# Rev2_Logicar.net
KiCad netlist of a schematic drawn in EAGLE
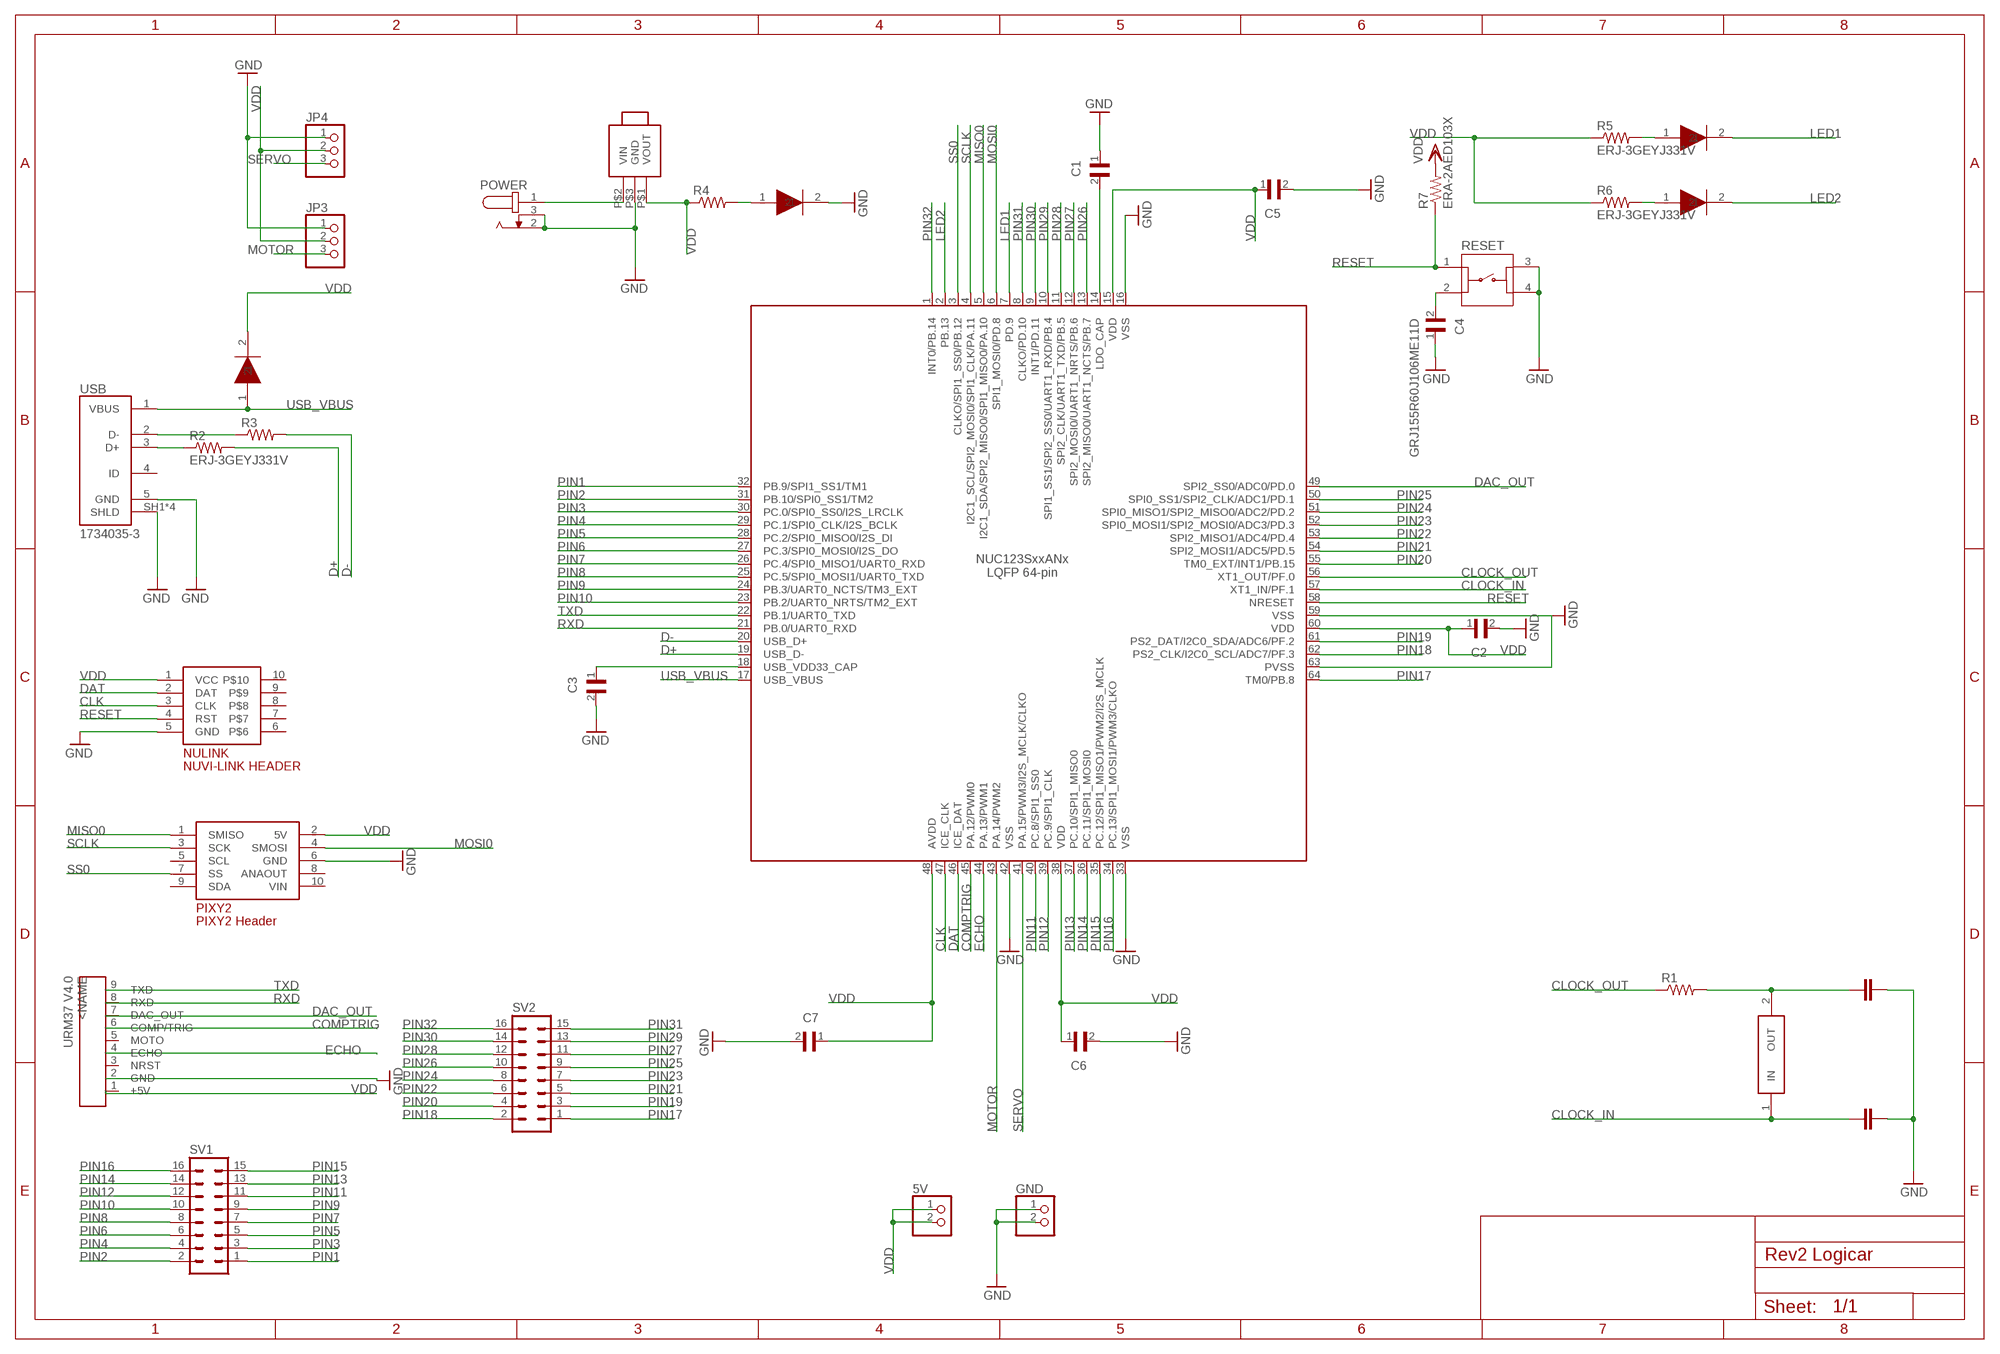
[diagram p0: schematic, sheet 1]

(export (version "E")
  (design (tool "Eeschema 10.0.6"))
  (components
    (comp (ref "5V")
      (value "PINHD-1X2")
      (footprint "eagle-import:1X02")
      (libsource (lib "eagle-import") (part "PINHD-1X2"))
    )
    (comp (ref "18UF")
      (value "18UF_CAPACITOR")
      (footprint "eagle-import:CAPC1608X70")
      (libsource (lib "eagle-import") (part "18UF_CAPACITOR"))
    )
    (comp (ref "18UF1")
      (value "18UF_CAPACITOR")
      (footprint "eagle-import:CAPC1608X70")
      (libsource (lib "eagle-import") (part "18UF_CAPACITOR"))
    )
    (comp (ref "C1")
      (value "F380J476MMAAXEH3")
      (footprint "eagle-import:CAPC1608X90")
      (fields (field (name "MF") "AVX"))
      (libsource (lib "eagle-import") (part "F380J476MMAAXEH3"))
    )
    (comp (ref "C2")
      (value "CL21F104ZBCNNNC")
      (footprint "eagle-import:CAPC2012X140N")
      (fields
        (field (name "DIGI-KEY_PART_NUMBER") "1276-1007-1-ND")
        (field (name "MF") "Samsung Electro-Mechanics")
      )
      (libsource (lib "eagle-import") (part "CL21F104ZBCNNNC"))
    )
    (comp (ref "C3")
      (value "CL21F104ZBCNNNC")
      (footprint "eagle-import:CAPC2012X140N")
      (fields
        (field (name "DIGI-KEY_PART_NUMBER") "1276-1007-1-ND")
        (field (name "MF") "Samsung Electro-Mechanics")
      )
      (libsource (lib "eagle-import") (part "CL21F104ZBCNNNC"))
    )
    (comp (ref "C4")
      (value "GRJ155R60J106ME11D")
      (footprint "eagle-import:CAPC1005X55N")
      (fields (field (name "DIGI-KEY_PART_NUMBER") "490-13211-1-ND") (field (name "MF") "Murata"))
      (libsource (lib "eagle-import") (part "GRJ155R60J106ME11D"))
    )
    (comp (ref "C5")
      (value "CL21F104ZBCNNNC")
      (footprint "eagle-import:CAPC2012X140N")
      (fields
        (field (name "DIGI-KEY_PART_NUMBER") "1276-1007-1-ND")
        (field (name "MF") "Samsung Electro-Mechanics")
      )
      (libsource (lib "eagle-import") (part "CL21F104ZBCNNNC"))
    )
    (comp (ref "C6")
      (value "CL21F104ZBCNNNC")
      (footprint "eagle-import:CAPC2012X140N")
      (fields
        (field (name "DIGI-KEY_PART_NUMBER") "1276-1007-1-ND")
        (field (name "MF") "Samsung Electro-Mechanics")
      )
      (libsource (lib "eagle-import") (part "CL21F104ZBCNNNC"))
    )
    (comp (ref "C7")
      (value "CL21F104ZBCNNNC")
      (footprint "eagle-import:CAPC2012X140N")
      (fields
        (field (name "DIGI-KEY_PART_NUMBER") "1276-1007-1-ND")
        (field (name "MF") "Samsung Electro-Mechanics")
      )
      (libsource (lib "eagle-import") (part "CL21F104ZBCNNNC"))
    )
    (comp (ref "GND")
      (value "PINHD-1X2")
      (footprint "eagle-import:1X02")
      (libsource (lib "eagle-import") (part "PINHD-1X2"))
    )
    (comp (ref "JP3")
      (value "PINHD-1X3")
      (footprint "eagle-import:1X03")
      (libsource (lib "eagle-import") (part "PINHD-1X3"))
    )
    (comp (ref "JP4")
      (value "PINHD-1X3")
      (footprint "eagle-import:1X03")
      (libsource (lib "eagle-import") (part "PINHD-1X3"))
    )
    (comp (ref "LED1")
      (value "LED")
      (footprint "eagle-import:LEDC2408X70")
      (libsource (lib "eagle-import") (part "LED"))
    )
    (comp (ref "LED2")
      (value "LED")
      (footprint "eagle-import:LEDC2408X70")
      (libsource (lib "eagle-import") (part "LED"))
    )
    (comp (ref "NUC123")
      (value "NUC123SD4AN0-ND")
      (footprint "eagle-import:QFP40P900X900X160-64")
      (libsource (lib "eagle-import") (part "NUC123SD4AN0-ND"))
    )
    (comp (ref "NULINK")
      (value "NUVI-LINK")
      (footprint "eagle-import:NUVI-LINK")
      (libsource (lib "eagle-import") (part "NUVI-LINK"))
    )
    (comp (ref "PIXY2")
      (value "PIXY2HEADER")
      (footprint "eagle-import:PIXY2PIN")
      (libsource (lib "eagle-import") (part "PIXY2HEADER"))
    )
    (comp (ref "POWER")
      (value "PJ-202A")
      (footprint "eagle-import:CUI_PJ-202A")
      (fields (field (name "DIGI-KEY_PART_NUMBER") "CP-202A-ND") (field (name "MF") "CUI Inc."))
      (libsource (lib "eagle-import") (part "PJ-202A"))
    )
    (comp (ref "PWR_LED")
      (value "LED")
      (footprint "eagle-import:LEDC2408X70")
      (libsource (lib "eagle-import") (part "LED"))
    )
    (comp (ref "R1")
      (value "ERJ-3GEYJ331V")
      (footprint "eagle-import:RESC1608X55")
      (fields (field (name "DIGI-KEY_PART_NUMBER") "P330GCT-ND") (field (name "MF") "Panasonic"))
      (libsource (lib "eagle-import") (part "ERJ-3GEYJ331V"))
    )
    (comp (ref "R2")
      (value "ERJ-3GEYJ331V")
      (footprint "eagle-import:RESC1608X55")
      (fields (field (name "DIGI-KEY_PART_NUMBER") "P330GCT-ND") (field (name "MF") "Panasonic"))
      (libsource (lib "eagle-import") (part "ERJ-3GEYJ331V"))
    )
    (comp (ref "R3")
      (value "ERJ-3GEYJ331V")
      (footprint "eagle-import:RESC1608X55")
      (fields (field (name "DIGI-KEY_PART_NUMBER") "P330GCT-ND") (field (name "MF") "Panasonic"))
      (libsource (lib "eagle-import") (part "ERJ-3GEYJ331V"))
    )
    (comp (ref "R4")
      (value "ERJ-3GEYJ331V")
      (footprint "eagle-import:RESC1608X55")
      (fields (field (name "DIGI-KEY_PART_NUMBER") "P330GCT-ND") (field (name "MF") "Panasonic"))
      (libsource (lib "eagle-import") (part "ERJ-3GEYJ331V"))
    )
    (comp (ref "R5")
      (value "ERJ-3GEYJ331V")
      (footprint "eagle-import:RESC1608X55")
      (fields (field (name "DIGI-KEY_PART_NUMBER") "P330GCT-ND") (field (name "MF") "Panasonic"))
      (libsource (lib "eagle-import") (part "ERJ-3GEYJ331V"))
    )
    (comp (ref "R6")
      (value "ERJ-3GEYJ331V")
      (footprint "eagle-import:RESC1608X55")
      (fields (field (name "DIGI-KEY_PART_NUMBER") "P330GCT-ND") (field (name "MF") "Panasonic"))
      (libsource (lib "eagle-import") (part "ERJ-3GEYJ331V"))
    )
    (comp (ref "R7")
      (value "ERA-2AED103X")
      (footprint "eagle-import:RESC1005X40")
      (fields (field (name "DIGI-KEY_PART_NUMBER") "P10KDECT-ND") (field (name "MF") "Panasonic"))
      (libsource (lib "eagle-import") (part "ERA-2AED103X"))
    )
    (comp (ref "RESET")
      (value "1825910-6")
      (footprint "eagle-import:SW_1825910-6-4")
      (fields (field (name "DIGI-KEY_PART_NUMBER") "450-1650-ND") (field (name "MF") "TE Connectivity"))
      (libsource (lib "eagle-import") (part "1825910-6"))
    )
    (comp (ref "SV1")
      (value "MA08-2")
      (footprint "eagle-import:MA08-2")
      (libsource (lib "eagle-import") (part "MA08-2"))
    )
    (comp (ref "SV2")
      (value "MA08-2")
      (footprint "eagle-import:MA08-2")
      (libsource (lib "eagle-import") (part "MA08-2"))
    )
    (comp (ref "U$2")
      (value "CRYSTAL_OSS")
      (footprint "eagle-import:XTAL1145X470X420")
      (libsource (lib "eagle-import") (part "CRYSTAL_OSS"))
    )
    (comp (ref "U$8")
      (value "NCP5501")
      (footprint "eagle-import:DPAK3")
      (libsource (lib "eagle-import") (part "NCP5501"))
    )
    (comp (ref "ULTRASONIC")
      (value "1X9PINROW_MALE")
      (footprint "eagle-import:HDRV9W64P254_1X9_1016X508X838B")
      (libsource (lib "eagle-import") (part "1X9PINROW_MALE"))
    )
    (comp (ref "USB")
      (value "1734035-3")
      (footprint "eagle-import:TE_1734035-3")
      (fields (field (name "DIGI-KEY_PART_NUMBER") "A121553CT-ND") (field (name "MF") "TE Connectivity"))
      (libsource (lib "eagle-import") (part "1734035-3"))
    )
    (comp (ref "USB_LED")
      (value "LED")
      (footprint "eagle-import:LEDC2408X70")
      (libsource (lib "eagle-import") (part "LED"))
    )
  )
  (nets
    (net (code "1") (name "/CLK") (class "Default")
      (node (ref "NUC123") (pin "47") (pinfunction "ICE_CLK_47") (pintype "bidirectional"))
      (node (ref "NULINK") (pin "3") (pinfunction "CLK_3") (pintype "bidirectional"))
    )
    (net (code "2") (name "/CLOCK_IN") (class "Default")
      (node (ref "18UF") (pin "1") (pinfunction "1_1") (pintype "passive"))
      (node (ref "NUC123") (pin "57") (pinfunction "XT1_IN/PF.1_57") (pintype "bidirectional"))
      (node (ref "U$2") (pin "1") (pinfunction "IN_1") (pintype "bidirectional"))
    )
    (net (code "3") (name "/CLOCK_OUT") (class "Default")
      (node (ref "NUC123") (pin "56") (pinfunction "XT1_OUT/PF.0_56") (pintype "bidirectional"))
      (node (ref "R1") (pin "1") (pinfunction "1_1") (pintype "passive"))
    )
    (net (code "4") (name "/COMPTRIG") (class "Default")
      (node (ref "NUC123") (pin "45") (pinfunction "PA.12/PWM0_45") (pintype "bidirectional"))
      (node (ref "ULTRASONIC") (pin "6") (pinfunction "COMP/TRIG_6") (pintype "bidirectional"))
    )
    (net (code "5") (name "/D+") (class "Default")
      (node (ref "NUC123") (pin "19") (pinfunction "USB_D-_19") (pintype "bidirectional"))
      (node (ref "R2") (pin "2") (pinfunction "2_2") (pintype "passive"))
    )
    (net (code "6") (name "/D-") (class "Default")
      (node (ref "NUC123") (pin "20") (pinfunction "USB_D+_20") (pintype "bidirectional"))
      (node (ref "R3") (pin "2") (pinfunction "2_2") (pintype "passive"))
    )
    (net (code "7") (name "/DAC_OUT") (class "Default")
      (node (ref "NUC123") (pin "49") (pinfunction "SPI2_SS0/ADC0/PD.0_49") (pintype "bidirectional"))
      (node (ref "ULTRASONIC") (pin "7") (pinfunction "DAC_OUT_7") (pintype "bidirectional"))
    )
    (net (code "8") (name "/DAT") (class "Default")
      (node (ref "NUC123") (pin "46") (pinfunction "ICE_DAT_46") (pintype "bidirectional"))
      (node (ref "NULINK") (pin "2") (pinfunction "DAT_2") (pintype "bidirectional"))
    )
    (net (code "9") (name "/ECHO") (class "Default")
      (node (ref "NUC123") (pin "44") (pinfunction "PA.13/PWM1_44") (pintype "bidirectional"))
      (node (ref "ULTRASONIC") (pin "4") (pinfunction "ECHO_4") (pintype "bidirectional"))
    )
    (net (code "10") (name "/LED1") (class "Default")
      (node (ref "LED1") (pin "2") (pinfunction "2_2") (pintype "bidirectional"))
      (node (ref "NUC123") (pin "7") (pinfunction "PD.9_7") (pintype "bidirectional"))
    )
    (net (code "11") (name "/LED2") (class "Default")
      (node (ref "LED2") (pin "2") (pinfunction "2_2") (pintype "bidirectional"))
      (node (ref "NUC123") (pin "2") (pinfunction "PB.13_2") (pintype "bidirectional"))
    )
    (net (code "12") (name "/MISO0") (class "Default")
      (node (ref "NUC123") (pin "5") (pinfunction "I2C1_SDA/SPI2_MISO0/SPI1_MISO0/PA.10_5") (pintype "bidirectional"))
      (node (ref "PIXY2") (pin "1") (pinfunction "SMISO_1") (pintype "bidirectional"))
    )
    (net (code "13") (name "/MOSI0") (class "Default")
      (node (ref "NUC123") (pin "6") (pinfunction "SPI1_MOSI0/PD.8_6") (pintype "bidirectional"))
      (node (ref "PIXY2") (pin "4") (pinfunction "SMOSI_4") (pintype "bidirectional"))
    )
    (net (code "14") (name "/MOTOR") (class "Default")
      (node (ref "JP3") (pin "3") (pinfunction "3_3") (pintype "passive"))
      (node (ref "NUC123") (pin "43") (pinfunction "PA.14/PWM2_43") (pintype "bidirectional"))
    )
    (net (code "15") (name "/PIN1") (class "Default")
      (node (ref "NUC123") (pin "32") (pinfunction "PB.9/SPI1_SS1/TM1_32") (pintype "bidirectional"))
      (node (ref "SV1") (pin "1") (pinfunction "1_1") (pintype "passive"))
    )
    (net (code "16") (name "/PIN2") (class "Default")
      (node (ref "NUC123") (pin "31") (pinfunction "PB.10/SPI0_SS1/TM2_31") (pintype "bidirectional"))
      (node (ref "SV1") (pin "2") (pinfunction "2_2") (pintype "passive"))
    )
    (net (code "17") (name "/PIN3") (class "Default")
      (node (ref "NUC123") (pin "30") (pinfunction "PC.0/SPI0_SS0/I2S_LRCLK_30") (pintype "bidirectional"))
      (node (ref "SV1") (pin "3") (pinfunction "3_3") (pintype "passive"))
    )
    (net (code "18") (name "/PIN4") (class "Default")
      (node (ref "NUC123") (pin "29") (pinfunction "PC.1/SPI0_CLK/I2S_BCLK_29") (pintype "bidirectional"))
      (node (ref "SV1") (pin "4") (pinfunction "4_4") (pintype "passive"))
    )
    (net (code "19") (name "/PIN5") (class "Default")
      (node (ref "NUC123") (pin "28") (pinfunction "PC.2/SPI0_MISO0/I2S_DI_28") (pintype "bidirectional"))
      (node (ref "SV1") (pin "5") (pinfunction "5_5") (pintype "passive"))
    )
    (net (code "20") (name "/PIN6") (class "Default")
      (node (ref "NUC123") (pin "27") (pinfunction "PC.3/SPI0_MOSI0/I2S_DO_27") (pintype "bidirectional"))
      (node (ref "SV1") (pin "6") (pinfunction "6_6") (pintype "passive"))
    )
    (net (code "21") (name "/PIN7") (class "Default")
      (node (ref "NUC123") (pin "26") (pinfunction "PC.4/SPI0_MISO1/UART0_RXD_26") (pintype "bidirectional"))
      (node (ref "SV1") (pin "7") (pinfunction "7_7") (pintype "passive"))
    )
    (net (code "22") (name "/PIN8") (class "Default")
      (node (ref "NUC123") (pin "25") (pinfunction "PC.5/SPI0_MOSI1/UART0_TXD_25") (pintype "bidirectional"))
      (node (ref "SV1") (pin "8") (pinfunction "8_8") (pintype "passive"))
    )
    (net (code "23") (name "/PIN9") (class "Default")
      (node (ref "NUC123") (pin "24") (pinfunction "PB.3/UART0_NCTS/TM3_EXT_24") (pintype "bidirectional"))
      (node (ref "SV1") (pin "9") (pinfunction "9_9") (pintype "passive"))
    )
    (net (code "24") (name "/PIN10") (class "Default")
      (node (ref "NUC123") (pin "23") (pinfunction "PB.2/UART0_NRTS/TM2_EXT_23") (pintype "bidirectional"))
      (node (ref "SV1") (pin "10") (pinfunction "10_10") (pintype "passive"))
    )
    (net (code "25") (name "/PIN11") (class "Default")
      (node (ref "NUC123") (pin "40") (pinfunction "PC.8/SPI1_SS0_40") (pintype "bidirectional"))
      (node (ref "SV1") (pin "11") (pinfunction "11_11") (pintype "passive"))
    )
    (net (code "26") (name "/PIN12") (class "Default")
      (node (ref "NUC123") (pin "39") (pinfunction "PC.9/SPI1_CLK_39") (pintype "bidirectional"))
      (node (ref "SV1") (pin "12") (pinfunction "12_12") (pintype "passive"))
    )
    (net (code "27") (name "/PIN13") (class "Default")
      (node (ref "NUC123") (pin "37") (pinfunction "PC.10/SPI1_MISO0_37") (pintype "bidirectional"))
      (node (ref "SV1") (pin "13") (pinfunction "13_13") (pintype "passive"))
    )
    (net (code "28") (name "/PIN14") (class "Default")
      (node (ref "NUC123") (pin "36") (pinfunction "PC.11/SPI1_MOSI0_36") (pintype "bidirectional"))
      (node (ref "SV1") (pin "14") (pinfunction "14_14") (pintype "passive"))
    )
    (net (code "29") (name "/PIN15") (class "Default")
      (node (ref "NUC123") (pin "35") (pinfunction "PC.12/SPI1_MISO1/PWM2/I2S_MCLK_35") (pintype "bidirectional"))
      (node (ref "SV1") (pin "15") (pinfunction "15_15") (pintype "passive"))
    )
    (net (code "30") (name "/PIN16") (class "Default")
      (node (ref "NUC123") (pin "34") (pinfunction "PC.13/SPI1_MOSI1/PWM3/CLKO_34") (pintype "bidirectional"))
      (node (ref "SV1") (pin "16") (pinfunction "16_16") (pintype "passive"))
    )
    (net (code "31") (name "/PIN17") (class "Default")
      (node (ref "NUC123") (pin "64") (pinfunction "TM0/PB.8_64") (pintype "bidirectional"))
      (node (ref "SV2") (pin "1") (pinfunction "1_1") (pintype "passive"))
    )
    (net (code "32") (name "/PIN18") (class "Default")
      (node (ref "NUC123") (pin "62") (pinfunction "PS2_CLK/I2C0_SCL/ADC7/PF.3_62") (pintype "bidirectional"))
      (node (ref "SV2") (pin "2") (pinfunction "2_2") (pintype "passive"))
    )
    (net (code "33") (name "/PIN19") (class "Default")
      (node (ref "NUC123") (pin "61") (pinfunction "PS2_DAT/I2C0_SDA/ADC6/PF.2_61") (pintype "bidirectional"))
      (node (ref "SV2") (pin "3") (pinfunction "3_3") (pintype "passive"))
    )
    (net (code "34") (name "/PIN20") (class "Default")
      (node (ref "NUC123") (pin "55") (pinfunction "TM0_EXT/INT1/PB.15_55") (pintype "bidirectional"))
      (node (ref "SV2") (pin "4") (pinfunction "4_4") (pintype "passive"))
    )
    (net (code "35") (name "/PIN21") (class "Default")
      (node (ref "NUC123") (pin "54") (pinfunction "SPI2_MOSI1/ADC5/PD.5_54") (pintype "bidirectional"))
      (node (ref "SV2") (pin "5") (pinfunction "5_5") (pintype "passive"))
    )
    (net (code "36") (name "/PIN22") (class "Default")
      (node (ref "NUC123") (pin "53") (pinfunction "SPI2_MISO1/ADC4/PD.4_53") (pintype "bidirectional"))
      (node (ref "SV2") (pin "6") (pinfunction "6_6") (pintype "passive"))
    )
    (net (code "37") (name "/PIN23") (class "Default")
      (node (ref "NUC123") (pin "52") (pinfunction "SPI0_MOSI1/SPI2_MOSI0/ADC3/PD.3_52") (pintype "bidirectional"))
      (node (ref "SV2") (pin "7") (pinfunction "7_7") (pintype "passive"))
    )
    (net (code "38") (name "/PIN24") (class "Default")
      (node (ref "NUC123") (pin "51") (pinfunction "SPI0_MISO1/SPI2_MISO0/ADC2/PD.2_51") (pintype "bidirectional"))
      (node (ref "SV2") (pin "8") (pinfunction "8_8") (pintype "passive"))
    )
    (net (code "39") (name "/PIN25") (class "Default")
      (node (ref "NUC123") (pin "50") (pinfunction "SPI0_SS1/SPI2_CLK/ADC1/PD.1_50") (pintype "bidirectional"))
      (node (ref "SV2") (pin "9") (pinfunction "9_9") (pintype "passive"))
    )
    (net (code "40") (name "/PIN26") (class "Default")
      (node (ref "NUC123") (pin "13") (pinfunction "SPI2_MISO0/UART1_NCTS/PB.7_13") (pintype "bidirectional"))
      (node (ref "SV2") (pin "10") (pinfunction "10_10") (pintype "passive"))
    )
    (net (code "41") (name "/PIN27") (class "Default")
      (node (ref "NUC123") (pin "12") (pinfunction "SPI2_MOSI0/UART1_NRTS/PB.6_12") (pintype "bidirectional"))
      (node (ref "SV2") (pin "11") (pinfunction "11_11") (pintype "passive"))
    )
    (net (code "42") (name "/PIN28") (class "Default")
      (node (ref "NUC123") (pin "11") (pinfunction "SPI2_CLK/UART1_TXD/PB.5_11") (pintype "bidirectional"))
      (node (ref "SV2") (pin "12") (pinfunction "12_12") (pintype "passive"))
    )
    (net (code "43") (name "/PIN29") (class "Default")
      (node (ref "NUC123") (pin "10") (pinfunction "SPI1_SS1/SPI2_SS0/UART1_RXD/PB.4_10") (pintype "bidirectional"))
      (node (ref "SV2") (pin "13") (pinfunction "13_13") (pintype "passive"))
    )
    (net (code "44") (name "/PIN30") (class "Default")
      (node (ref "NUC123") (pin "9") (pinfunction "INT1/PD.11_9") (pintype "bidirectional"))
      (node (ref "SV2") (pin "14") (pinfunction "14_14") (pintype "passive"))
    )
    (net (code "45") (name "/PIN31") (class "Default")
      (node (ref "NUC123") (pin "8") (pinfunction "CLKO/PD.10_8") (pintype "bidirectional"))
      (node (ref "SV2") (pin "15") (pinfunction "15_15") (pintype "passive"))
    )
    (net (code "46") (name "/PIN32") (class "Default")
      (node (ref "NUC123") (pin "1") (pinfunction "INT0/PB.14_1") (pintype "bidirectional"))
      (node (ref "SV2") (pin "16") (pinfunction "16_16") (pintype "passive"))
    )
    (net (code "47") (name "/RESET") (class "Default")
      (node (ref "NUC123") (pin "58") (pinfunction "NRESET_58") (pintype "bidirectional"))
      (node (ref "NULINK") (pin "4") (pinfunction "RST_4") (pintype "bidirectional"))
      (node (ref "R7") (pin "1") (pinfunction "1_1") (pintype "passive"))
      (node (ref "RESET") (pin "1") (pinfunction "1_1") (pintype "passive"))
    )
    (net (code "48") (name "/RXD") (class "Default")
      (node (ref "NUC123") (pin "21") (pinfunction "PB.0/UART0_RXD_21") (pintype "bidirectional"))
      (node (ref "ULTRASONIC") (pin "8") (pinfunction "RXD_8") (pintype "bidirectional"))
    )
    (net (code "49") (name "/SCLK") (class "Default")
      (node (ref "NUC123") (pin "4") (pinfunction "I2C1_SCL/SPI2_MOSI0/SPI1_CLK/PA.11_4") (pintype "bidirectional"))
      (node (ref "PIXY2") (pin "3") (pinfunction "SCK_3") (pintype "bidirectional"))
    )
    (net (code "50") (name "/SERVO") (class "Default")
      (node (ref "JP4") (pin "3") (pinfunction "3_3") (pintype "passive"))
      (node (ref "NUC123") (pin "41") (pinfunction "PA.15/PWM3/I2S_MCLK/CLKO_41") (pintype "bidirectional"))
    )
    (net (code "51") (name "/SS0") (class "Default")
      (node (ref "NUC123") (pin "3") (pinfunction "CLKO/SPI1_SS0/PB.12_3") (pintype "bidirectional"))
      (node (ref "PIXY2") (pin "7") (pinfunction "SS_7") (pintype "bidirectional"))
    )
    (net (code "52") (name "/TXD") (class "Default")
      (node (ref "NUC123") (pin "22") (pinfunction "PB.1/UART0_TXD_22") (pintype "bidirectional"))
      (node (ref "ULTRASONIC") (pin "9") (pinfunction "TXD_9") (pintype "bidirectional"))
    )
    (net (code "53") (name "/USB_VBUS") (class "Default")
      (node (ref "NUC123") (pin "17") (pinfunction "USB_VBUS_17") (pintype "bidirectional"))
      (node (ref "USB") (pin "1") (pinfunction "VBUS_1") (pintype "passive"))
      (node (ref "USB_LED") (pin "1") (pinfunction "1_1") (pintype "bidirectional"))
    )
    (net (code "54") (name "GND") (class "Default")
      (node (ref "18UF") (pin "2") (pinfunction "2_2") (pintype "passive"))
      (node (ref "18UF1") (pin "2") (pinfunction "2_2") (pintype "passive"))
      (node (ref "C1") (pin "1") (pinfunction "1_1") (pintype "passive"))
      (node (ref "C2") (pin "2") (pinfunction "2_2") (pintype "passive"))
      (node (ref "C3") (pin "2") (pinfunction "2_2") (pintype "passive"))
      (node (ref "C4") (pin "1") (pinfunction "1_1") (pintype "passive"))
      (node (ref "C5") (pin "2") (pinfunction "2_2") (pintype "passive"))
      (node (ref "C6") (pin "2") (pinfunction "2_2") (pintype "passive"))
      (node (ref "C7") (pin "2") (pinfunction "2_2") (pintype "passive"))
      (node (ref "GND") (pin "1") (pinfunction "1_1") (pintype "passive"))
      (node (ref "GND") (pin "2") (pinfunction "2_2") (pintype "passive"))
      (node (ref "JP3") (pin "1") (pinfunction "1_1") (pintype "passive"))
      (node (ref "JP4") (pin "1") (pinfunction "1_1") (pintype "passive"))
      (node (ref "NUC123") (pin "16") (pinfunction "VSS_16") (pintype "bidirectional"))
      (node (ref "NUC123") (pin "33") (pinfunction "VSS_33") (pintype "bidirectional"))
      (node (ref "NUC123") (pin "42") (pinfunction "VSS_42") (pintype "bidirectional"))
      (node (ref "NUC123") (pin "59") (pinfunction "VSS_59") (pintype "bidirectional"))
      (node (ref "NUC123") (pin "63") (pinfunction "PVSS_63") (pintype "bidirectional"))
      (node (ref "NULINK") (pin "5") (pinfunction "GND_5") (pintype "bidirectional"))
      (node (ref "PIXY2") (pin "6") (pinfunction "GND_6") (pintype "bidirectional"))
      (node (ref "POWER") (pin "2") (pinfunction "2_2") (pintype "passive"))
      (node (ref "POWER") (pin "3") (pinfunction "3_3") (pintype "passive"))
      (node (ref "PWR_LED") (pin "2") (pinfunction "2_2") (pintype "bidirectional"))
      (node (ref "RESET") (pin "3") (pinfunction "3_3") (pintype "passive"))
      (node (ref "RESET") (pin "4") (pinfunction "4_4") (pintype "passive"))
      (node (ref "U$8") (pin "P$3") (pinfunction "GND_P$3") (pintype "bidirectional"))
      (node (ref "ULTRASONIC") (pin "2") (pinfunction "GND_2") (pintype "bidirectional"))
      (node (ref "USB") (pin "5") (pinfunction "GND_5") (pintype "passive"))
      (node (ref "USB") (pin "SH1") (pinfunction "SHLD_SH1") (pintype "passive"))
      (node (ref "USB") (pin "SH2") (pinfunction "SHLD_SH2") (pintype "passive"))
      (node (ref "USB") (pin "SH3") (pinfunction "SHLD_SH3") (pintype "passive"))
      (node (ref "USB") (pin "SH4") (pinfunction "SHLD_SH4") (pintype "passive"))
    )
    (net (code "55") (name "Net-(C4-Pad2)") (class "Default")
      (node (ref "C4") (pin "2") (pinfunction "2_2") (pintype "passive"))
      (node (ref "RESET") (pin "2") (pinfunction "2_2") (pintype "passive"))
    )
    (net (code "56") (name "Net-(LED1-Pad1)") (class "Default")
      (node (ref "LED1") (pin "1") (pinfunction "1_1") (pintype "bidirectional"))
      (node (ref "R5") (pin "2") (pinfunction "2_2") (pintype "passive"))
    )
    (net (code "57") (name "Net-(LED2-Pad1)") (class "Default")
      (node (ref "LED2") (pin "1") (pinfunction "1_1") (pintype "bidirectional"))
      (node (ref "R6") (pin "2") (pinfunction "2_2") (pintype "passive"))
    )
    (net (code "58") (name "Net-(NUC123-LDO_CAP)") (class "Default")
      (node (ref "C1") (pin "2") (pinfunction "2_2") (pintype "passive"))
      (node (ref "NUC123") (pin "14") (pinfunction "LDO_CAP_14") (pintype "bidirectional"))
    )
    (net (code "59") (name "Net-(NUC123-USB_VDD33_CAP)") (class "Default")
      (node (ref "C3") (pin "1") (pinfunction "1_1") (pintype "passive"))
      (node (ref "NUC123") (pin "18") (pinfunction "USB_VDD33_CAP_18") (pintype "bidirectional"))
    )
    (net (code "60") (name "Net-(PWR_LED-Pad1)") (class "Default")
      (node (ref "PWR_LED") (pin "1") (pinfunction "1_1") (pintype "bidirectional"))
      (node (ref "R4") (pin "2") (pinfunction "2_2") (pintype "passive"))
    )
    (net (code "61") (name "Net-(U$2-OUT)") (class "Default")
      (node (ref "18UF1") (pin "1") (pinfunction "1_1") (pintype "passive"))
      (node (ref "R1") (pin "2") (pinfunction "2_2") (pintype "passive"))
      (node (ref "U$2") (pin "2") (pinfunction "OUT_2") (pintype "bidirectional"))
    )
    (net (code "62") (name "Net-(U$8-VIN)") (class "Default")
      (node (ref "POWER") (pin "1") (pinfunction "1_1") (pintype "passive"))
      (node (ref "U$8") (pin "P$2") (pinfunction "VIN_P$2") (pintype "bidirectional"))
    )
    (net (code "63") (name "Net-(USB-D+)") (class "Default")
      (node (ref "R2") (pin "1") (pinfunction "1_1") (pintype "passive"))
      (node (ref "USB") (pin "3") (pinfunction "D+_3") (pintype "passive"))
    )
    (net (code "64") (name "Net-(USB-D-)") (class "Default")
      (node (ref "R3") (pin "1") (pinfunction "1_1") (pintype "passive"))
      (node (ref "USB") (pin "2") (pinfunction "D-_2") (pintype "passive"))
    )
    (net (code "65") (name "VDD") (class "Default")
      (node (ref "5V") (pin "1") (pinfunction "1_1") (pintype "passive"))
      (node (ref "5V") (pin "2") (pinfunction "2_2") (pintype "passive"))
      (node (ref "C2") (pin "1") (pinfunction "1_1") (pintype "passive"))
      (node (ref "C5") (pin "1") (pinfunction "1_1") (pintype "passive"))
      (node (ref "C6") (pin "1") (pinfunction "1_1") (pintype "passive"))
      (node (ref "C7") (pin "1") (pinfunction "1_1") (pintype "passive"))
      (node (ref "JP3") (pin "2") (pinfunction "2_2") (pintype "passive"))
      (node (ref "JP4") (pin "2") (pinfunction "2_2") (pintype "passive"))
      (node (ref "NUC123") (pin "15") (pinfunction "VDD_15") (pintype "bidirectional"))
      (node (ref "NUC123") (pin "38") (pinfunction "VDD_38") (pintype "bidirectional"))
      (node (ref "NUC123") (pin "48") (pinfunction "AVDD_48") (pintype "bidirectional"))
      (node (ref "NUC123") (pin "60") (pinfunction "VDD_60") (pintype "bidirectional"))
      (node (ref "NULINK") (pin "1") (pinfunction "VCC_1") (pintype "bidirectional"))
      (node (ref "PIXY2") (pin "2") (pinfunction "5V_2") (pintype "bidirectional"))
      (node (ref "R4") (pin "1") (pinfunction "1_1") (pintype "passive"))
      (node (ref "R5") (pin "1") (pinfunction "1_1") (pintype "passive"))
      (node (ref "R6") (pin "1") (pinfunction "1_1") (pintype "passive"))
      (node (ref "R7") (pin "2") (pinfunction "2_2") (pintype "passive"))
      (node (ref "U$8") (pin "P$1") (pinfunction "VOUT_P$1") (pintype "bidirectional"))
      (node (ref "ULTRASONIC") (pin "1") (pinfunction "+5V_1") (pintype "bidirectional"))
      (node (ref "USB_LED") (pin "2") (pinfunction "2_2") (pintype "bidirectional"))
    )
    (net (code "66") (name "unconnected-(NULINK-P$6-Pad6)") (class "Default")
      (node (ref "NULINK") (pin "6") (pinfunction "P$6_6") (pintype "bidirectional"))
    )
    (net (code "67") (name "unconnected-(NULINK-P$7-Pad7)") (class "Default")
      (node (ref "NULINK") (pin "7") (pinfunction "P$7_7") (pintype "bidirectional"))
    )
    (net (code "68") (name "unconnected-(NULINK-P$8-Pad8)") (class "Default")
      (node (ref "NULINK") (pin "8") (pinfunction "P$8_8") (pintype "bidirectional"))
    )
    (net (code "69") (name "unconnected-(NULINK-P$9-Pad9)") (class "Default")
      (node (ref "NULINK") (pin "9") (pinfunction "P$9_9") (pintype "bidirectional"))
    )
    (net (code "70") (name "unconnected-(NULINK-P$10-Pad10)") (class "Default")
      (node (ref "NULINK") (pin "10") (pinfunction "P$10_10") (pintype "bidirectional"))
    )
    (net (code "71") (name "unconnected-(PIXY2-ANAOUT-Pad8)") (class "Default")
      (node (ref "PIXY2") (pin "8") (pinfunction "ANAOUT_8") (pintype "bidirectional"))
    )
    (net (code "72") (name "unconnected-(PIXY2-SCL-Pad5)") (class "Default")
      (node (ref "PIXY2") (pin "5") (pinfunction "SCL_5") (pintype "bidirectional"))
    )
    (net (code "73") (name "unconnected-(PIXY2-SDA-Pad9)") (class "Default")
      (node (ref "PIXY2") (pin "9") (pinfunction "SDA_9") (pintype "bidirectional"))
    )
    (net (code "74") (name "unconnected-(PIXY2-VIN-Pad10)") (class "Default")
      (node (ref "PIXY2") (pin "10") (pinfunction "VIN_10") (pintype "bidirectional"))
    )
    (net (code "75") (name "unconnected-(ULTRASONIC-MOTO-Pad5)") (class "Default")
      (node (ref "ULTRASONIC") (pin "5") (pinfunction "MOTO_5") (pintype "bidirectional"))
    )
    (net (code "76") (name "unconnected-(ULTRASONIC-NRST-Pad3)") (class "Default")
      (node (ref "ULTRASONIC") (pin "3") (pinfunction "NRST_3") (pintype "bidirectional"))
    )
    (net (code "77") (name "unconnected-(USB-ID-Pad4)") (class "Default")
      (node (ref "USB") (pin "4") (pinfunction "ID_4") (pintype "passive"))
    )
  )
)
